# ESP32_breakout_v3.net
KiCad netlist of a schematic drawn in EAGLE
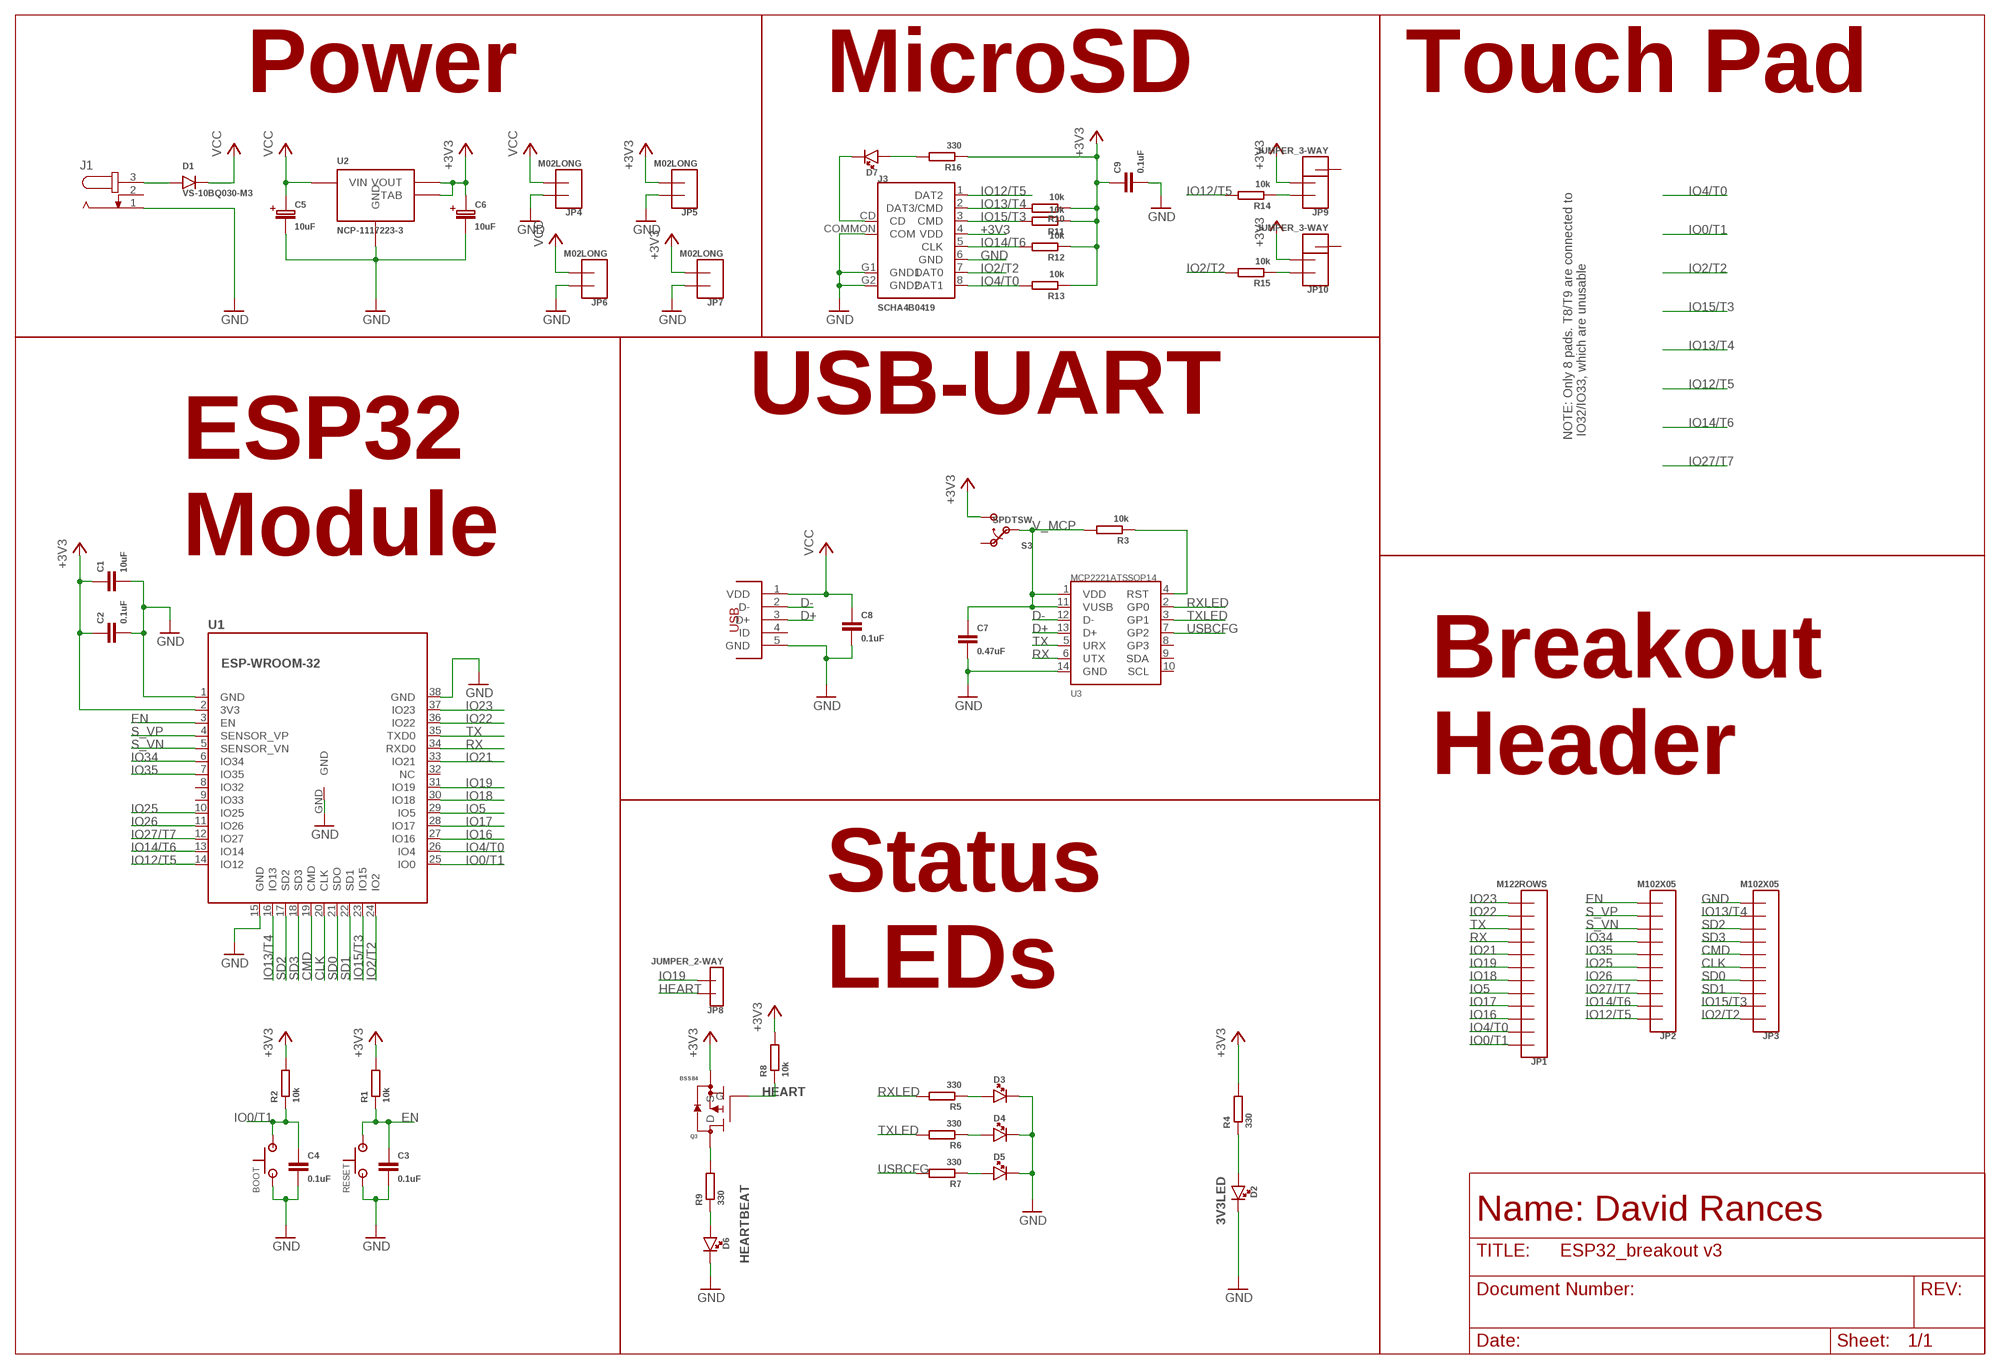
[diagram p0: schematic, sheet 1]

(export (version "E")
  (design (tool "Eeschema 10.0.6"))
  (components
    (comp (ref "BOOT")
      (value "PUSHBUTTONSKHMQME010")
      (footprint "eagle-import:SKHMQME010")
      (libsource (lib "eagle-import") (part "PUSHBUTTONSKHMQME010"))
    )
    (comp (ref "C1")
      (value "10uF")
      (footprint "eagle-import:CAP-0603")
      (libsource (lib "eagle-import") (part "CAP0603"))
    )
    (comp (ref "C2")
      (value "0.1uF")
      (footprint "eagle-import:CAP-0603")
      (libsource (lib "eagle-import") (part "CAP0603"))
    )
    (comp (ref "C3")
      (value "0.1uF")
      (footprint "eagle-import:CAP-0603")
      (libsource (lib "eagle-import") (part "CAP0603"))
    )
    (comp (ref "C4")
      (value "0.1uF")
      (footprint "eagle-import:CAP-0603")
      (libsource (lib "eagle-import") (part "CAP0603"))
    )
    (comp (ref "C5")
      (value "10uF")
      (footprint "eagle-import:B-3528")
      (libsource (lib "eagle-import") (part "CAP-POLARCASEB-3528"))
    )
    (comp (ref "C6")
      (value "10uF")
      (footprint "eagle-import:B-3528")
      (libsource (lib "eagle-import") (part "CAP-POLARCASEB-3528"))
    )
    (comp (ref "C7")
      (value "0.47uF")
      (footprint "eagle-import:CAP-0603")
      (libsource (lib "eagle-import") (part "CAP0603"))
    )
    (comp (ref "C8")
      (value "0.1uF")
      (footprint "eagle-import:CAP-0603")
      (libsource (lib "eagle-import") (part "CAP0603"))
    )
    (comp (ref "C9")
      (value "0.1uF")
      (footprint "eagle-import:CAP-0603")
      (libsource (lib "eagle-import") (part "CAP0603"))
    )
    (comp (ref "D1")
      (value "VS-10BQ030-M3")
      (footprint "eagle-import:DO-214AA")
      (libsource (lib "eagle-import") (part "VS-10BQ030-M3"))
    )
    (comp (ref "D2")
      (value "LED1206")
      (footprint "eagle-import:LED-1206")
      (libsource (lib "eagle-import") (part "LED1206"))
    )
    (comp (ref "D3")
      (value "LED1206")
      (footprint "eagle-import:LED-1206")
      (libsource (lib "eagle-import") (part "LED1206"))
    )
    (comp (ref "D4")
      (value "LED1206")
      (footprint "eagle-import:LED-1206")
      (libsource (lib "eagle-import") (part "LED1206"))
    )
    (comp (ref "D5")
      (value "LED1206")
      (footprint "eagle-import:LED-1206")
      (libsource (lib "eagle-import") (part "LED1206"))
    )
    (comp (ref "D6")
      (value "LED1206")
      (footprint "eagle-import:LED-1206")
      (libsource (lib "eagle-import") (part "LED1206"))
    )
    (comp (ref "D7")
      (value "LED1206")
      (footprint "eagle-import:LED-1206")
      (libsource (lib "eagle-import") (part "LED1206"))
    )
    (comp (ref "J1")
      (value "JACK-PLUG0")
      (footprint "eagle-import:SPC4077")
      (libsource (lib "eagle-import") (part "JACK-PLUG0"))
    )
    (comp (ref "J3")
      (value "SCHA4B0419")
      (footprint "eagle-import:MICROSD_SCHA4B0419")
      (libsource (lib "eagle-import") (part "SCHA4B0419"))
    )
    (comp (ref "JP1")
      (value "M122ROWS")
      (footprint "eagle-import:2X06")
      (libsource (lib "eagle-import") (part "M122ROWS"))
    )
    (comp (ref "JP2")
      (value "M102X05")
      (footprint "eagle-import:2X05")
      (libsource (lib "eagle-import") (part "M102X05"))
    )
    (comp (ref "JP3")
      (value "M102X05")
      (footprint "eagle-import:2X05")
      (libsource (lib "eagle-import") (part "M102X05"))
    )
    (comp (ref "JP4")
      (value "M02LONG")
      (footprint "eagle-import:1X02-LONG")
      (libsource (lib "eagle-import") (part "M02LONG"))
    )
    (comp (ref "JP5")
      (value "M02LONG")
      (footprint "eagle-import:1X02-LONG")
      (libsource (lib "eagle-import") (part "M02LONG"))
    )
    (comp (ref "JP6")
      (value "M02LONG")
      (footprint "eagle-import:1X02-LONG")
      (libsource (lib "eagle-import") (part "M02LONG"))
    )
    (comp (ref "JP7")
      (value "M02LONG")
      (footprint "eagle-import:1X02-LONG")
      (libsource (lib "eagle-import") (part "M02LONG"))
    )
    (comp (ref "JP8")
      (value "JUMPER_2-WAY")
      (footprint "eagle-import:1X02")
      (libsource (lib "eagle-import") (part "JUMPER_2-WAY"))
    )
    (comp (ref "JP9")
      (value "JUMPER_3-WAY")
      (footprint "eagle-import:1X03")
      (libsource (lib "eagle-import") (part "JUMPER_3-WAY"))
    )
    (comp (ref "JP10")
      (value "JUMPER_3-WAY")
      (footprint "eagle-import:1X03")
      (libsource (lib "eagle-import") (part "JUMPER_3-WAY"))
    )
    (comp (ref "Q3")
      (value "BSS84")
      (footprint "eagle-import:SOT-23-3")
      (libsource (lib "eagle-import") (part "BSS84"))
    )
    (comp (ref "R1")
      (value "10k")
      (footprint "eagle-import:RES-0603")
      (libsource (lib "eagle-import") (part "RESISTOR0603"))
    )
    (comp (ref "R2")
      (value "10k")
      (footprint "eagle-import:RES-0603")
      (libsource (lib "eagle-import") (part "RESISTOR0603"))
    )
    (comp (ref "R3")
      (value "10k")
      (footprint "eagle-import:RES-0603")
      (libsource (lib "eagle-import") (part "RESISTOR0603"))
    )
    (comp (ref "R4")
      (value "330")
      (footprint "eagle-import:RES-0603")
      (libsource (lib "eagle-import") (part "RESISTOR0603"))
    )
    (comp (ref "R5")
      (value "330")
      (footprint "eagle-import:RES-0603")
      (libsource (lib "eagle-import") (part "RESISTOR0603"))
    )
    (comp (ref "R6")
      (value "330")
      (footprint "eagle-import:RES-0603")
      (libsource (lib "eagle-import") (part "RESISTOR0603"))
    )
    (comp (ref "R7")
      (value "330")
      (footprint "eagle-import:RES-0603")
      (libsource (lib "eagle-import") (part "RESISTOR0603"))
    )
    (comp (ref "R8")
      (value "10k")
      (footprint "eagle-import:RES-0603")
      (libsource (lib "eagle-import") (part "RESISTOR0603"))
    )
    (comp (ref "R9")
      (value "330")
      (footprint "eagle-import:RES-0603")
      (libsource (lib "eagle-import") (part "RESISTOR0603"))
    )
    (comp (ref "R10")
      (value "10k")
      (footprint "eagle-import:RES-0603")
      (libsource (lib "eagle-import") (part "RESISTOR0603"))
    )
    (comp (ref "R11")
      (value "10k")
      (footprint "eagle-import:RES-0603")
      (libsource (lib "eagle-import") (part "RESISTOR0603"))
    )
    (comp (ref "R12")
      (value "10k")
      (footprint "eagle-import:RES-0603")
      (libsource (lib "eagle-import") (part "RESISTOR0603"))
    )
    (comp (ref "R13")
      (value "10k")
      (footprint "eagle-import:RES-0603")
      (libsource (lib "eagle-import") (part "RESISTOR0603"))
    )
    (comp (ref "R14")
      (value "10k")
      (footprint "eagle-import:RES-0603")
      (libsource (lib "eagle-import") (part "RESISTOR0603"))
    )
    (comp (ref "R15")
      (value "10k")
      (footprint "eagle-import:RES-0603")
      (libsource (lib "eagle-import") (part "RESISTOR0603"))
    )
    (comp (ref "R16")
      (value "330")
      (footprint "eagle-import:RES-0603")
      (libsource (lib "eagle-import") (part "RESISTOR0603"))
    )
    (comp (ref "RESET")
      (value "PUSHBUTTONSKHMQME010")
      (footprint "eagle-import:SKHMQME010")
      (libsource (lib "eagle-import") (part "PUSHBUTTONSKHMQME010"))
    )
    (comp (ref "S3")
      (value "SPDTSW")
      (footprint "eagle-import:SPDT_TH")
      (libsource (lib "eagle-import") (part "SPDTSW"))
    )
    (comp (ref "U$4")
      (value "MOLEX_USBMICRO")
      (footprint "eagle-import:MOLEX_47346-001")
      (libsource (lib "eagle-import") (part "MOLEX_USBMICRO"))
    )
    (comp (ref "U1")
      (value "ESP-WROOM-32")
      (footprint "eagle-import:ESP-WROOM-32")
      (libsource (lib "eagle-import") (part "ESP-WROOM-32"))
    )
    (comp (ref "U2")
      (value "NCP-1117223-3")
      (footprint "eagle-import:SOT-223-3")
      (libsource (lib "eagle-import") (part "NCP-1117223-3"))
    )
    (comp (ref "U3")
      (value "MCP2221ATSSOP14")
      (footprint "eagle-import:TSSOP-14")
      (libsource (lib "eagle-import") (part "MCP2221ATSSOP14"))
    )
  )
  (nets
    (net (code "1") (name "+3V3") (class "Default")
      (node (ref "C1") (pin "1") (pinfunction "1_1") (pintype "passive"))
      (node (ref "C2") (pin "1") (pinfunction "1_1") (pintype "passive"))
      (node (ref "C6") (pin "P") (pinfunction "P_P") (pintype "passive"))
      (node (ref "C9") (pin "1") (pinfunction "1_1") (pintype "passive"))
      (node (ref "J3") (pin "4") (pinfunction "VDD_4") (pintype "bidirectional"))
      (node (ref "JP10") (pin "2") (pinfunction "2_2") (pintype "bidirectional"))
      (node (ref "JP5") (pin "2") (pinfunction "2_2") (pintype "bidirectional"))
      (node (ref "JP7") (pin "2") (pinfunction "2_2") (pintype "bidirectional"))
      (node (ref "JP9") (pin "2") (pinfunction "2_2") (pintype "bidirectional"))
      (node (ref "Q3") (pin "S") (pinfunction "S_S") (pintype "bidirectional"))
      (node (ref "R1") (pin "2") (pinfunction "2_2") (pintype "passive"))
      (node (ref "R10") (pin "1") (pinfunction "1_1") (pintype "passive"))
      (node (ref "R11") (pin "1") (pinfunction "1_1") (pintype "passive"))
      (node (ref "R12") (pin "1") (pinfunction "1_1") (pintype "passive"))
      (node (ref "R13") (pin "1") (pinfunction "1_1") (pintype "passive"))
      (node (ref "R16") (pin "1") (pinfunction "1_1") (pintype "passive"))
      (node (ref "R2") (pin "2") (pinfunction "2_2") (pintype "passive"))
      (node (ref "R4") (pin "2") (pinfunction "2_2") (pintype "passive"))
      (node (ref "R8") (pin "2") (pinfunction "2_2") (pintype "passive"))
      (node (ref "S3") (pin "3") (pinfunction "2_3") (pintype "bidirectional"))
      (node (ref "U1") (pin "2") (pinfunction "3V3_2") (pintype "bidirectional"))
      (node (ref "U2") (pin "2") (pinfunction "VOUT_2") (pintype "power_in"))
      (node (ref "U2") (pin "PAD") (pinfunction "TAB_PAD") (pintype "power_in"))
    )
    (net (code "2") (name "/CLK") (class "Default")
      (node (ref "JP3") (pin "5") (pinfunction "5_5") (pintype "bidirectional"))
      (node (ref "U1") (pin "20") (pinfunction "CLK_20") (pintype "bidirectional"))
    )
    (net (code "3") (name "/CMD") (class "Default")
      (node (ref "JP3") (pin "6") (pinfunction "6_6") (pintype "bidirectional"))
      (node (ref "U1") (pin "19") (pinfunction "CMD_19") (pintype "bidirectional"))
    )
    (net (code "4") (name "/D+") (class "Default")
      (node (ref "U$4") (pin "3") (pinfunction "D+_3") (pintype "bidirectional"))
      (node (ref "U3") (pin "13") (pinfunction "D+_13") (pintype "bidirectional"))
    )
    (net (code "5") (name "/D-") (class "Default")
      (node (ref "U$4") (pin "2") (pinfunction "D-_2") (pintype "bidirectional"))
      (node (ref "U3") (pin "12") (pinfunction "D-_12") (pintype "bidirectional"))
    )
    (net (code "6") (name "/EN") (class "Default")
      (node (ref "C3") (pin "1") (pinfunction "1_1") (pintype "passive"))
      (node (ref "JP2") (pin "10") (pinfunction "10_10") (pintype "bidirectional"))
      (node (ref "R1") (pin "1") (pinfunction "1_1") (pintype "passive"))
      (node (ref "RESET") (pin "3") (pinfunction "2_3") (pintype "bidirectional"))
      (node (ref "RESET") (pin "4") (pinfunction "2_4") (pintype "bidirectional"))
      (node (ref "U1") (pin "3") (pinfunction "EN_3") (pintype "bidirectional"))
    )
    (net (code "7") (name "/HEART") (class "Default")
      (node (ref "JP8") (pin "1") (pinfunction "1_1") (pintype "bidirectional"))
      (node (ref "Q3") (pin "G") (pinfunction "G_G") (pintype "bidirectional"))
      (node (ref "R8") (pin "1") (pinfunction "1_1") (pintype "passive"))
    )
    (net (code "8") (name "/IO0{slash}T1") (class "Default")
      (node (ref "BOOT") (pin "3") (pinfunction "2_3") (pintype "bidirectional"))
      (node (ref "BOOT") (pin "4") (pinfunction "2_4") (pintype "bidirectional"))
      (node (ref "C4") (pin "1") (pinfunction "1_1") (pintype "passive"))
      (node (ref "JP1") (pin "1") (pinfunction "1_1") (pintype "bidirectional"))
      (node (ref "R2") (pin "1") (pinfunction "1_1") (pintype "passive"))
      (node (ref "U1") (pin "25") (pinfunction "IO0_25") (pintype "bidirectional"))
    )
    (net (code "9") (name "/IO2{slash}T2") (class "Default")
      (node (ref "J3") (pin "7") (pinfunction "DAT0_7") (pintype "bidirectional"))
      (node (ref "JP3") (pin "1") (pinfunction "1_1") (pintype "bidirectional"))
      (node (ref "R15") (pin "2") (pinfunction "2_2") (pintype "passive"))
      (node (ref "U1") (pin "24") (pinfunction "IO2_24") (pintype "bidirectional"))
    )
    (net (code "10") (name "/IO4{slash}T0") (class "Default")
      (node (ref "J3") (pin "8") (pinfunction "DAT1_8") (pintype "bidirectional"))
      (node (ref "JP1") (pin "2") (pinfunction "2_2") (pintype "bidirectional"))
      (node (ref "R13") (pin "2") (pinfunction "2_2") (pintype "passive"))
      (node (ref "U1") (pin "26") (pinfunction "IO4_26") (pintype "bidirectional"))
    )
    (net (code "11") (name "/IO5") (class "Default")
      (node (ref "JP1") (pin "5") (pinfunction "5_5") (pintype "bidirectional"))
      (node (ref "U1") (pin "29") (pinfunction "IO5_29") (pintype "bidirectional"))
    )
    (net (code "12") (name "/IO12{slash}T5") (class "Default")
      (node (ref "J3") (pin "1") (pinfunction "DAT2_1") (pintype "bidirectional"))
      (node (ref "JP2") (pin "1") (pinfunction "1_1") (pintype "bidirectional"))
      (node (ref "R14") (pin "2") (pinfunction "2_2") (pintype "passive"))
      (node (ref "U1") (pin "14") (pinfunction "IO12_14") (pintype "bidirectional"))
    )
    (net (code "13") (name "/IO13{slash}T4") (class "Default")
      (node (ref "J3") (pin "2") (pinfunction "DAT3/CMD_2") (pintype "bidirectional"))
      (node (ref "JP3") (pin "9") (pinfunction "9_9") (pintype "bidirectional"))
      (node (ref "R10") (pin "2") (pinfunction "2_2") (pintype "passive"))
      (node (ref "U1") (pin "16") (pinfunction "IO13_16") (pintype "bidirectional"))
    )
    (net (code "14") (name "/IO14{slash}T6") (class "Default")
      (node (ref "J3") (pin "5") (pinfunction "CLK_5") (pintype "bidirectional"))
      (node (ref "JP2") (pin "2") (pinfunction "2_2") (pintype "bidirectional"))
      (node (ref "R12") (pin "2") (pinfunction "2_2") (pintype "passive"))
      (node (ref "U1") (pin "13") (pinfunction "IO14_13") (pintype "bidirectional"))
    )
    (net (code "15") (name "/IO15{slash}T3") (class "Default")
      (node (ref "J3") (pin "3") (pinfunction "CMD_3") (pintype "bidirectional"))
      (node (ref "JP3") (pin "2") (pinfunction "2_2") (pintype "bidirectional"))
      (node (ref "R11") (pin "2") (pinfunction "2_2") (pintype "passive"))
      (node (ref "U1") (pin "23") (pinfunction "IO15_23") (pintype "bidirectional"))
    )
    (net (code "16") (name "/IO16") (class "Default")
      (node (ref "JP1") (pin "3") (pinfunction "3_3") (pintype "bidirectional"))
      (node (ref "U1") (pin "27") (pinfunction "IO16_27") (pintype "bidirectional"))
    )
    (net (code "17") (name "/IO17") (class "Default")
      (node (ref "JP1") (pin "4") (pinfunction "4_4") (pintype "bidirectional"))
      (node (ref "U1") (pin "28") (pinfunction "IO17_28") (pintype "bidirectional"))
    )
    (net (code "18") (name "/IO18") (class "Default")
      (node (ref "JP1") (pin "6") (pinfunction "6_6") (pintype "bidirectional"))
      (node (ref "U1") (pin "30") (pinfunction "IO18_30") (pintype "bidirectional"))
    )
    (net (code "19") (name "/IO19") (class "Default")
      (node (ref "JP1") (pin "7") (pinfunction "7_7") (pintype "bidirectional"))
      (node (ref "JP8") (pin "2") (pinfunction "2_2") (pintype "bidirectional"))
      (node (ref "U1") (pin "31") (pinfunction "IO19_31") (pintype "bidirectional"))
    )
    (net (code "20") (name "/IO21") (class "Default")
      (node (ref "JP1") (pin "8") (pinfunction "8_8") (pintype "bidirectional"))
      (node (ref "U1") (pin "33") (pinfunction "IO21_33") (pintype "bidirectional"))
    )
    (net (code "21") (name "/IO22") (class "Default")
      (node (ref "JP1") (pin "11") (pinfunction "11_11") (pintype "bidirectional"))
      (node (ref "U1") (pin "36") (pinfunction "IO22_36") (pintype "bidirectional"))
    )
    (net (code "22") (name "/IO23") (class "Default")
      (node (ref "JP1") (pin "12") (pinfunction "12_12") (pintype "bidirectional"))
      (node (ref "U1") (pin "37") (pinfunction "IO23_37") (pintype "bidirectional"))
    )
    (net (code "23") (name "/IO25") (class "Default")
      (node (ref "JP2") (pin "5") (pinfunction "5_5") (pintype "bidirectional"))
      (node (ref "U1") (pin "10") (pinfunction "IO25_10") (pintype "bidirectional"))
    )
    (net (code "24") (name "/IO26") (class "Default")
      (node (ref "JP2") (pin "4") (pinfunction "4_4") (pintype "bidirectional"))
      (node (ref "U1") (pin "11") (pinfunction "IO26_11") (pintype "bidirectional"))
    )
    (net (code "25") (name "/IO27{slash}T7") (class "Default")
      (node (ref "JP2") (pin "3") (pinfunction "3_3") (pintype "bidirectional"))
      (node (ref "U1") (pin "12") (pinfunction "IO27_12") (pintype "bidirectional"))
    )
    (net (code "26") (name "/IO34") (class "Default")
      (node (ref "JP2") (pin "7") (pinfunction "7_7") (pintype "bidirectional"))
      (node (ref "U1") (pin "6") (pinfunction "IO34_6") (pintype "bidirectional"))
    )
    (net (code "27") (name "/IO35") (class "Default")
      (node (ref "JP2") (pin "6") (pinfunction "6_6") (pintype "bidirectional"))
      (node (ref "U1") (pin "7") (pinfunction "IO35_7") (pintype "bidirectional"))
    )
    (net (code "28") (name "/RX") (class "Default")
      (node (ref "JP1") (pin "9") (pinfunction "9_9") (pintype "bidirectional"))
      (node (ref "U1") (pin "34") (pinfunction "RXD0_34") (pintype "bidirectional"))
      (node (ref "U3") (pin "6") (pinfunction "UTX_6") (pintype "bidirectional"))
    )
    (net (code "29") (name "/RXLED") (class "Default")
      (node (ref "R5") (pin "2") (pinfunction "2_2") (pintype "passive"))
      (node (ref "U3") (pin "2") (pinfunction "GP0_2") (pintype "bidirectional"))
    )
    (net (code "30") (name "/SD0") (class "Default")
      (node (ref "JP3") (pin "4") (pinfunction "4_4") (pintype "bidirectional"))
      (node (ref "U1") (pin "21") (pinfunction "SDO_21") (pintype "bidirectional"))
    )
    (net (code "31") (name "/SD1") (class "Default")
      (node (ref "JP3") (pin "3") (pinfunction "3_3") (pintype "bidirectional"))
      (node (ref "U1") (pin "22") (pinfunction "SD1_22") (pintype "bidirectional"))
    )
    (net (code "32") (name "/SD2") (class "Default")
      (node (ref "JP3") (pin "8") (pinfunction "8_8") (pintype "bidirectional"))
      (node (ref "U1") (pin "17") (pinfunction "SD2_17") (pintype "bidirectional"))
    )
    (net (code "33") (name "/SD3") (class "Default")
      (node (ref "JP3") (pin "7") (pinfunction "7_7") (pintype "bidirectional"))
      (node (ref "U1") (pin "18") (pinfunction "SD3_18") (pintype "bidirectional"))
    )
    (net (code "34") (name "/S_VN") (class "Default")
      (node (ref "JP2") (pin "8") (pinfunction "8_8") (pintype "bidirectional"))
      (node (ref "U1") (pin "5") (pinfunction "SENSOR_VN_5") (pintype "bidirectional"))
    )
    (net (code "35") (name "/S_VP") (class "Default")
      (node (ref "JP2") (pin "9") (pinfunction "9_9") (pintype "bidirectional"))
      (node (ref "U1") (pin "4") (pinfunction "SENSOR_VP_4") (pintype "bidirectional"))
    )
    (net (code "36") (name "/TX") (class "Default")
      (node (ref "JP1") (pin "10") (pinfunction "10_10") (pintype "bidirectional"))
      (node (ref "U1") (pin "35") (pinfunction "TXD0_35") (pintype "bidirectional"))
      (node (ref "U3") (pin "5") (pinfunction "URX_5") (pintype "bidirectional"))
    )
    (net (code "37") (name "/TXLED") (class "Default")
      (node (ref "R6") (pin "2") (pinfunction "2_2") (pintype "passive"))
      (node (ref "U3") (pin "3") (pinfunction "GP1_3") (pintype "bidirectional"))
    )
    (net (code "38") (name "/USBCFG") (class "Default")
      (node (ref "R7") (pin "2") (pinfunction "2_2") (pintype "passive"))
      (node (ref "U3") (pin "7") (pinfunction "GP2_7") (pintype "bidirectional"))
    )
    (net (code "39") (name "/V_MCP") (class "Default")
      (node (ref "C7") (pin "1") (pinfunction "1_1") (pintype "passive"))
      (node (ref "R3") (pin "2") (pinfunction "2_2") (pintype "passive"))
      (node (ref "S3") (pin "2") (pinfunction "OUT_2") (pintype "bidirectional"))
      (node (ref "U3") (pin "1") (pinfunction "VDD_1") (pintype "bidirectional"))
      (node (ref "U3") (pin "11") (pinfunction "VUSB_11") (pintype "bidirectional"))
    )
    (net (code "40") (name "GND") (class "Default")
      (node (ref "BOOT") (pin "1") (pinfunction "1_1") (pintype "bidirectional"))
      (node (ref "BOOT") (pin "2") (pinfunction "1_2") (pintype "bidirectional"))
      (node (ref "C1") (pin "2") (pinfunction "2_2") (pintype "passive"))
      (node (ref "C2") (pin "2") (pinfunction "2_2") (pintype "passive"))
      (node (ref "C3") (pin "2") (pinfunction "2_2") (pintype "passive"))
      (node (ref "C4") (pin "2") (pinfunction "2_2") (pintype "passive"))
      (node (ref "C5") (pin "N") (pinfunction "N_N") (pintype "passive"))
      (node (ref "C6") (pin "N") (pinfunction "N_N") (pintype "passive"))
      (node (ref "C7") (pin "2") (pinfunction "2_2") (pintype "passive"))
      (node (ref "C8") (pin "2") (pinfunction "2_2") (pintype "passive"))
      (node (ref "C9") (pin "2") (pinfunction "2_2") (pintype "passive"))
      (node (ref "D2") (pin "C") (pinfunction "C_C") (pintype "bidirectional"))
      (node (ref "D3") (pin "C") (pinfunction "C_C") (pintype "bidirectional"))
      (node (ref "D4") (pin "C") (pinfunction "C_C") (pintype "bidirectional"))
      (node (ref "D5") (pin "C") (pinfunction "C_C") (pintype "bidirectional"))
      (node (ref "D6") (pin "C") (pinfunction "C_C") (pintype "bidirectional"))
      (node (ref "J1") (pin "1") (pinfunction "1_1") (pintype "passive"))
      (node (ref "J3") (pin "6") (pinfunction "GND_6") (pintype "bidirectional"))
      (node (ref "J3") (pin "COMMON") (pinfunction "COM_COMMON") (pintype "bidirectional"))
      (node (ref "J3") (pin "G1") (pinfunction "GND1_G1") (pintype "bidirectional"))
      (node (ref "J3") (pin "G2") (pinfunction "GND2_G2") (pintype "bidirectional"))
      (node (ref "JP3") (pin "10") (pinfunction "10_10") (pintype "bidirectional"))
      (node (ref "JP4") (pin "1") (pinfunction "1_1") (pintype "bidirectional"))
      (node (ref "JP5") (pin "1") (pinfunction "1_1") (pintype "bidirectional"))
      (node (ref "JP6") (pin "1") (pinfunction "1_1") (pintype "bidirectional"))
      (node (ref "JP7") (pin "1") (pinfunction "1_1") (pintype "bidirectional"))
      (node (ref "RESET") (pin "1") (pinfunction "1_1") (pintype "bidirectional"))
      (node (ref "RESET") (pin "2") (pinfunction "1_2") (pintype "bidirectional"))
      (node (ref "U$4") (pin "5") (pinfunction "GND_5") (pintype "bidirectional"))
      (node (ref "U1") (pin "1") (pinfunction "GND_1") (pintype "bidirectional"))
      (node (ref "U1") (pin "15") (pinfunction "GND_15") (pintype "bidirectional"))
      (node (ref "U1") (pin "38") (pinfunction "GND_38") (pintype "bidirectional"))
      (node (ref "U1") (pin "GND") (pinfunction "GND_GND") (pintype "bidirectional"))
      (node (ref "U2") (pin "1") (pinfunction "GND_1") (pintype "power_in"))
      (node (ref "U3") (pin "14") (pinfunction "GND_14") (pintype "bidirectional"))
    )
    (net (code "41") (name "Net-(D1-PadA)") (class "Default")
      (node (ref "D1") (pin "A") (pinfunction "A_A") (pintype "bidirectional"))
      (node (ref "J1") (pin "3") (pinfunction "3_3") (pintype "passive"))
    )
    (net (code "42") (name "Net-(D2-PadA)") (class "Default")
      (node (ref "D2") (pin "A") (pinfunction "A_A") (pintype "bidirectional"))
      (node (ref "R4") (pin "1") (pinfunction "1_1") (pintype "passive"))
    )
    (net (code "43") (name "Net-(D3-PadA)") (class "Default")
      (node (ref "D3") (pin "A") (pinfunction "A_A") (pintype "bidirectional"))
      (node (ref "R5") (pin "1") (pinfunction "1_1") (pintype "passive"))
    )
    (net (code "44") (name "Net-(D4-PadA)") (class "Default")
      (node (ref "D4") (pin "A") (pinfunction "A_A") (pintype "bidirectional"))
      (node (ref "R6") (pin "1") (pinfunction "1_1") (pintype "passive"))
    )
    (net (code "45") (name "Net-(D5-PadA)") (class "Default")
      (node (ref "D5") (pin "A") (pinfunction "A_A") (pintype "bidirectional"))
      (node (ref "R7") (pin "1") (pinfunction "1_1") (pintype "passive"))
    )
    (net (code "46") (name "Net-(D6-PadA)") (class "Default")
      (node (ref "D6") (pin "A") (pinfunction "A_A") (pintype "bidirectional"))
      (node (ref "R9") (pin "1") (pinfunction "1_1") (pintype "passive"))
    )
    (net (code "47") (name "Net-(D7-PadA)") (class "Default")
      (node (ref "D7") (pin "A") (pinfunction "A_A") (pintype "bidirectional"))
      (node (ref "R16") (pin "2") (pinfunction "2_2") (pintype "passive"))
    )
    (net (code "48") (name "Net-(D7-PadC)") (class "Default")
      (node (ref "D7") (pin "C") (pinfunction "C_C") (pintype "bidirectional"))
      (node (ref "J3") (pin "CD") (pinfunction "CD_CD") (pintype "bidirectional"))
    )
    (net (code "49") (name "Net-(JP9-Pad1)") (class "Default")
      (node (ref "JP9") (pin "1") (pinfunction "1_1") (pintype "bidirectional"))
      (node (ref "R14") (pin "1") (pinfunction "1_1") (pintype "passive"))
    )
    (net (code "50") (name "Net-(JP10-Pad1)") (class "Default")
      (node (ref "JP10") (pin "1") (pinfunction "1_1") (pintype "bidirectional"))
      (node (ref "R15") (pin "1") (pinfunction "1_1") (pintype "passive"))
    )
    (net (code "51") (name "Net-(Q3-PadD)") (class "Default")
      (node (ref "Q3") (pin "D") (pinfunction "D_D") (pintype "bidirectional"))
      (node (ref "R9") (pin "2") (pinfunction "2_2") (pintype "passive"))
    )
    (net (code "52") (name "Net-(U3-RST)") (class "Default")
      (node (ref "R3") (pin "1") (pinfunction "1_1") (pintype "passive"))
      (node (ref "U3") (pin "4") (pinfunction "RST_4") (pintype "bidirectional"))
    )
    (net (code "53") (name "VCC") (class "Default")
      (node (ref "C5") (pin "P") (pinfunction "P_P") (pintype "passive"))
      (node (ref "C8") (pin "1") (pinfunction "1_1") (pintype "passive"))
      (node (ref "D1") (pin "C") (pinfunction "C_C") (pintype "bidirectional"))
      (node (ref "JP4") (pin "2") (pinfunction "2_2") (pintype "bidirectional"))
      (node (ref "JP6") (pin "2") (pinfunction "2_2") (pintype "bidirectional"))
      (node (ref "U$4") (pin "1") (pinfunction "VDD_1") (pintype "bidirectional"))
      (node (ref "U2") (pin "3") (pinfunction "VIN_3") (pintype "power_in"))
    )
    (net (code "54") (name "unconnected-(BOOT-3-Pad5)") (class "Default")
      (node (ref "BOOT") (pin "5") (pinfunction "3_5") (pintype "bidirectional"))
    )
    (net (code "55") (name "unconnected-(J1-Pad2)") (class "Default")
      (node (ref "J1") (pin "2") (pinfunction "2_2") (pintype "passive"))
    )
    (net (code "56") (name "unconnected-(JP9-Pad3)") (class "Default")
      (node (ref "JP9") (pin "3") (pinfunction "3_3") (pintype "bidirectional"))
    )
    (net (code "57") (name "unconnected-(JP10-Pad3)") (class "Default")
      (node (ref "JP10") (pin "3") (pinfunction "3_3") (pintype "bidirectional"))
    )
    (net (code "58") (name "unconnected-(RESET-3-Pad5)") (class "Default")
      (node (ref "RESET") (pin "5") (pinfunction "3_5") (pintype "bidirectional"))
    )
    (net (code "59") (name "unconnected-(S3-Pad1)") (class "Default")
      (node (ref "S3") (pin "1") (pinfunction "1_1") (pintype "bidirectional"))
    )
    (net (code "60") (name "unconnected-(U$4-ID-Pad4)") (class "Default")
      (node (ref "U$4") (pin "4") (pinfunction "ID_4") (pintype "bidirectional"))
    )
    (net (code "61") (name "unconnected-(U1-IO32-Pad8)") (class "Default")
      (node (ref "U1") (pin "8") (pinfunction "IO32_8") (pintype "bidirectional"))
    )
    (net (code "62") (name "unconnected-(U1-IO33-Pad9)") (class "Default")
      (node (ref "U1") (pin "9") (pinfunction "IO33_9") (pintype "bidirectional"))
    )
    (net (code "63") (name "unconnected-(U1-NC-Pad32)") (class "Default")
      (node (ref "U1") (pin "32") (pinfunction "NC_32") (pintype "bidirectional"))
    )
    (net (code "64") (name "unconnected-(U3-GP3-Pad8)") (class "Default")
      (node (ref "U3") (pin "8") (pinfunction "GP3_8") (pintype "bidirectional"))
    )
    (net (code "65") (name "unconnected-(U3-SCL-Pad10)") (class "Default")
      (node (ref "U3") (pin "10") (pinfunction "SCL_10") (pintype "bidirectional"))
    )
    (net (code "66") (name "unconnected-(U3-SDA-Pad9)") (class "Default")
      (node (ref "U3") (pin "9") (pinfunction "SDA_9") (pintype "bidirectional"))
    )
  )
)
